# bug1.net
KiCad netlist of a schematic drawn in EAGLE
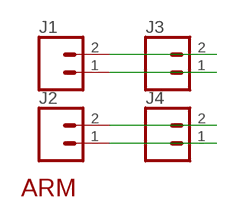
[diagram p0: schematic, sheet 1]

(export (version "E")
  (design (tool "Eeschema 10.0.6"))
  (components
    (comp (ref "J1")
      (value "CONN_02LOCK")
      (footprint "eagle-import:1X02_LOCK")
      (libsource (lib "eagle-import") (part "CONN_02LOCK"))
    )
    (comp (ref "J2")
      (value "CONN_02LOCK")
      (footprint "eagle-import:1X02_LOCK")
      (libsource (lib "eagle-import") (part "CONN_02LOCK"))
    )
    (comp (ref "J3")
      (value "CONN_02LOCK")
      (footprint "eagle-import:1X02_LOCK")
      (libsource (lib "eagle-import") (part "CONN_02LOCK"))
    )
    (comp (ref "J4")
      (value "CONN_02LOCK")
      (footprint "eagle-import:1X02_LOCK")
      (libsource (lib "eagle-import") (part "CONN_02LOCK"))
    )
    (comp (ref "U$1")
      (value "ARMBUG1")
      (footprint "eagle-import:BUG1")
      (libsource (lib "eagle-import") (part "ARMBUG1"))
    )
  )
  (nets
    (net (code "1") (name "Net-(J1-Pad1)") (class "Default")
      (node (ref "J1") (pin "1") (pinfunction "1_1") (pintype "passive"))
      (node (ref "J3") (pin "1") (pinfunction "1_1") (pintype "passive"))
    )
    (net (code "2") (name "Net-(J1-Pad2)") (class "Default")
      (node (ref "J1") (pin "2") (pinfunction "2_2") (pintype "passive"))
      (node (ref "J3") (pin "2") (pinfunction "2_2") (pintype "passive"))
    )
    (net (code "3") (name "Net-(J2-Pad1)") (class "Default")
      (node (ref "J2") (pin "1") (pinfunction "1_1") (pintype "passive"))
      (node (ref "J4") (pin "1") (pinfunction "1_1") (pintype "passive"))
    )
    (net (code "4") (name "Net-(J2-Pad2)") (class "Default")
      (node (ref "J2") (pin "2") (pinfunction "2_2") (pintype "passive"))
      (node (ref "J4") (pin "2") (pinfunction "2_2") (pintype "passive"))
    )
  )
)
